# 9_Axis_Sensor.net
KiCad netlist of a schematic drawn in Altium Designer
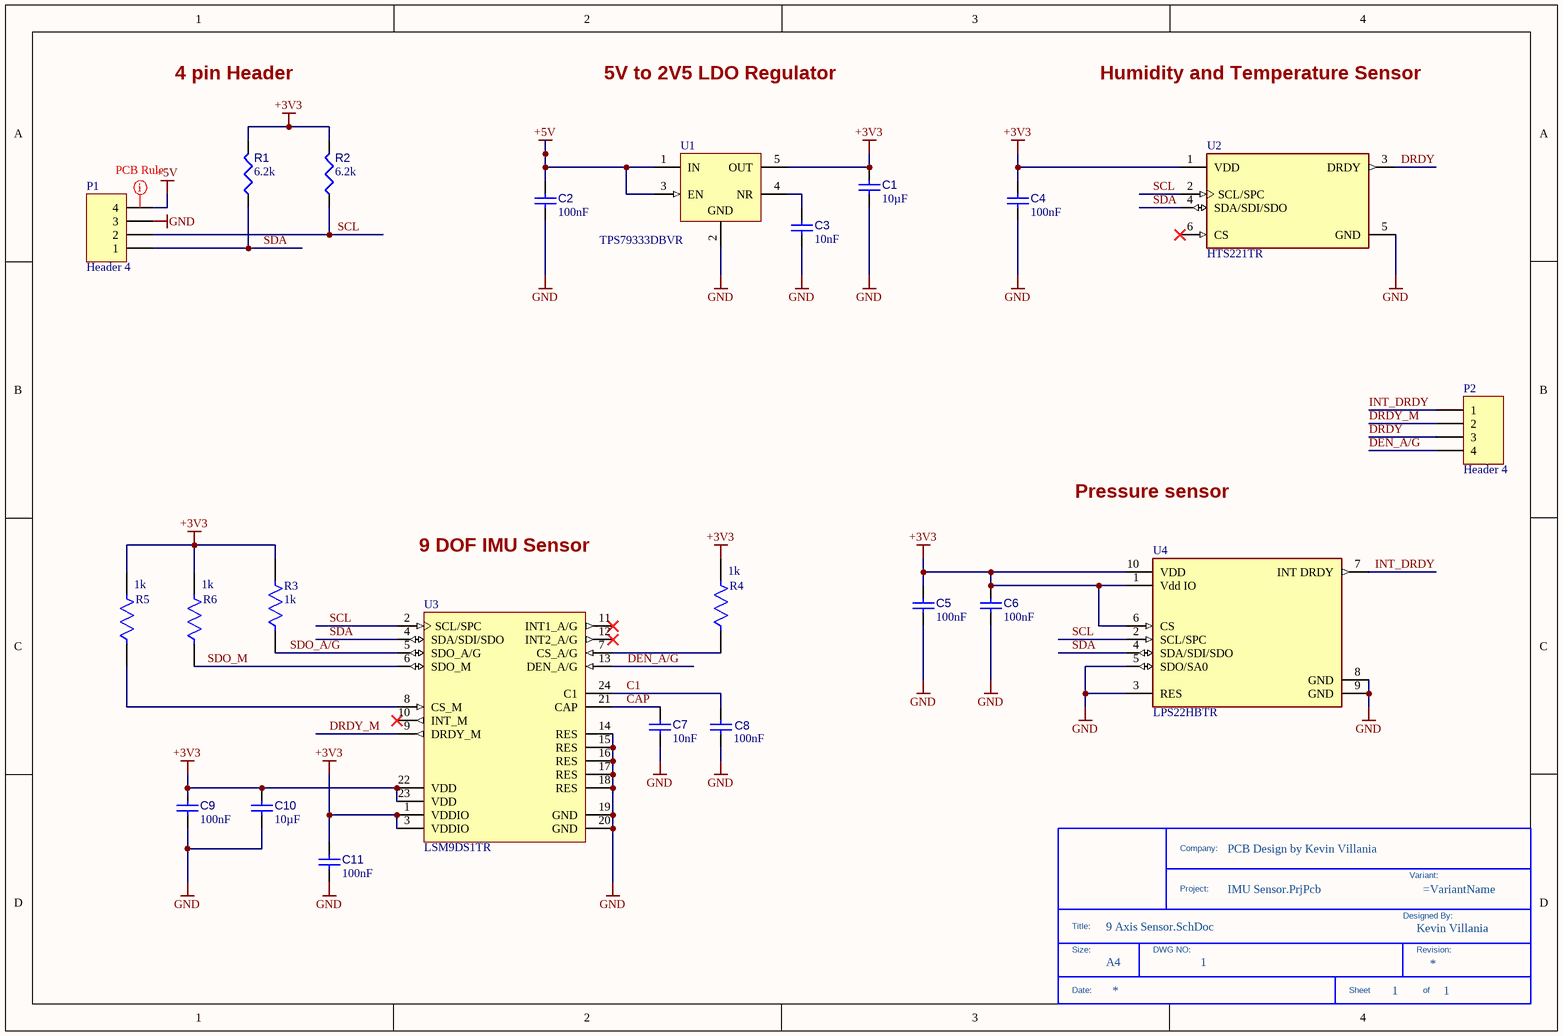
[diagram p0: 9 Axis Sensor.SchDoc]

(export (version "E")
  (design (tool "Eeschema 10.0.6"))
  (components
    (comp (ref "*")
      (value "Title Block")
      (description "Standard Title Block")
      (fields
        (field (name "DESIGNED BY") "Kevin Villania")
        (field (name "DWG NO") "1")
        (field (name "SIZE") "A4")
      )
      (libsource (lib "Standard Title Block Template") (part "Title Block"))
    )
    (comp (ref "C1")
      (value "10µF")
      (footprint "CAPC0402(1005)60_L")
      (description "Chip Capacitor, 10µF +/-40%, 6.3V, 0402, Thickness 0.6 mm")
      (fields (field (name "TOLERANCE") "10%") (field (name "Comment") "Capacitor 10µF +/-40% 6.3V 0402"))
      (libsource (lib "Polytechnic University of the Philippines") (part "CAP-NP-2"))
    )
    (comp (ref "C2")
      (value "100nF")
      (footprint "CAPC0402(1005)60_L")
      (description "Chip Capacitor, 100nF +/-20%, 10V, 0402, Thickness 0.6 mm")
      (fields (field (name "TOLERANCE") "20%") (field (name "Comment") "Capacitor 100nF +/-20% 10V 0402"))
      (libsource (lib "Polytechnic University of the Philippines") (part "CAP-NP-2"))
    )
    (comp (ref "C3")
      (value "10nF")
      (footprint "CAPC0402(1005)60_L")
      (description "Chip Capacitor, 10nF +/-20%, 50V, 0402, Thickness 0.6 mm")
      (fields (field (name "TOLERANCE") "5%") (field (name "Comment") "Capacitor 10nF +/-20% 50V 0402"))
      (libsource (lib "Polytechnic University of the Philippines") (part "CAP-NP-2"))
    )
    (comp (ref "C4")
      (value "100nF")
      (footprint "CAPC0402(1005)60_L")
      (description "Chip Capacitor, 100nF +/-20%, 10V, 0402, Thickness 0.6 mm")
      (fields (field (name "TOLERANCE") "20%") (field (name "Comment") "Capacitor 100nF +/-20% 10V 0402"))
      (libsource (lib "Polytechnic University of the Philippines") (part "CAP-NP-2"))
    )
    (comp (ref "C5")
      (value "100nF")
      (footprint "CAPC0402(1005)60_L")
      (description "Chip Capacitor, 100nF +/-20%, 10V, 0402, Thickness 0.6 mm")
      (fields (field (name "TOLERANCE") "20%") (field (name "Comment") "Capacitor 100nF +/-20% 10V 0402"))
      (libsource (lib "Polytechnic University of the Philippines") (part "CAP-NP-2"))
    )
    (comp (ref "C6")
      (value "100nF")
      (footprint "CAPC0402(1005)60_L")
      (description "Chip Capacitor, 100nF +/-20%, 10V, 0402, Thickness 0.6 mm")
      (fields (field (name "TOLERANCE") "20%") (field (name "Comment") "Capacitor 100nF +/-20% 10V 0402"))
      (libsource (lib "Polytechnic University of the Philippines") (part "CAP-NP-2"))
    )
    (comp (ref "C7")
      (value "10nF")
      (footprint "CAPC0402(1005)60_L")
      (description "Chip Capacitor, 10nF +/-20%, 50V, 0402, Thickness 0.6 mm")
      (fields (field (name "TOLERANCE") "5%") (field (name "Comment") "Capacitor 10nF +/-20% 50V 0402"))
      (libsource (lib "Polytechnic University of the Philippines") (part "CAP-NP-2"))
    )
    (comp (ref "C8")
      (value "100nF")
      (footprint "CAPC0402(1005)60_L")
      (description "Chip Capacitor, 100nF +/-20%, 10V, 0402, Thickness 0.6 mm")
      (fields (field (name "TOLERANCE") "20%") (field (name "Comment") "Capacitor 100nF +/-20% 10V 0402"))
      (libsource (lib "Polytechnic University of the Philippines") (part "CAP-NP-2"))
    )
    (comp (ref "C9")
      (value "100nF")
      (footprint "CAPC0402(1005)60_L")
      (description "Chip Capacitor, 100nF +/-20%, 10V, 0402, Thickness 0.6 mm")
      (fields (field (name "TOLERANCE") "20%") (field (name "Comment") "Capacitor 100nF +/-20% 10V 0402"))
      (libsource (lib "Polytechnic University of the Philippines") (part "CAP-NP-2"))
    )
    (comp (ref "C10")
      (value "10µF")
      (footprint "CAPC0603(1608)100_L")
      (description "Chip Capacitor, 10µF +/-20%, 10V, 0603, Thickness 1 mm")
      (fields (field (name "TOLERANCE") "10%") (field (name "Comment") "Capacitor 10µF +/-20% 10V 0603"))
      (libsource (lib "Polytechnic University of the Philippines") (part "CAP-NP-2"))
    )
    (comp (ref "C11")
      (value "100nF")
      (footprint "CAPC0402(1005)60_L")
      (description "Chip Capacitor, 100nF +/-20%, 10V, 0402, Thickness 0.6 mm")
      (fields (field (name "TOLERANCE") "20%") (field (name "Comment") "Capacitor 100nF +/-20% 10V 0402"))
      (libsource (lib "Polytechnic University of the Philippines") (part "CAP-NP-2"))
    )
    (comp (ref "P1")
      (value "Header 4")
      (footprint "HDR1X4")
      (description "Header, 4-Pin")
      (fields (field (name "PUBLISHER") "Altium Limited"))
      (libsource (lib "Miscellaneous Connectors") (part "Header 4"))
    )
    (comp (ref "P2")
      (value "Header 4")
      (footprint "HDR1X4")
      (description "Header, 4-Pin")
      (fields (field (name "PUBLISHER") "Altium Limited"))
      (libsource (lib "") (part "Header 4_1"))
    )
    (comp (ref "R1")
      (value "6.2k")
      (footprint "RESC0402(1005)_L")
      (description "Chip Resistor, 6,2 kOhms, +/-5 %, 63 mW, -55 to 155 degC, 0402")
      (fields (field (name "TOLERANCE") "5%") (field (name "POWER") "63mW"))
      (libsource (lib "Polytechnic University of the Philippines") (part "RES-2"))
    )
    (comp (ref "R2")
      (value "6.2k")
      (footprint "RESC0402(1005)_L")
      (description "Chip Resistor, 6,2 kOhms, +/-5 %, 63 mW, -55 to 155 degC, 0402")
      (fields (field (name "TOLERANCE") "5%") (field (name "POWER") "63mW"))
      (libsource (lib "Polytechnic University of the Philippines") (part "RES-2"))
    )
    (comp (ref "R3")
      (value "1k")
      (footprint "FP-RC1005-IPC_A")
      (description "Res Thick Film 0402 1kΩ 1% 0.063W ±100ppm/°C Molded SMD T/R")
      (fields (field (name "TOLERANCE") "1%"))
      (libsource (lib "Altium Content Vault") (part "1029c3af85768c4190bb7ad29bc67b5"))
    )
    (comp (ref "R4")
      (value "1k")
      (footprint "FP-RC1005-IPC_A")
      (description "Res Thick Film 0402 1kΩ 1% 0.063W ±100ppm/°C Molded SMD T/R")
      (fields (field (name "TOLERANCE") "1%"))
      (libsource (lib "Altium Content Vault") (part "1029c3af85768c4190bb7ad29bc67b5"))
    )
    (comp (ref "R5")
      (value "1k")
      (footprint "FP-RC1005-IPC_A")
      (description "Res Thick Film 0402 1kΩ 1% 0.063W ±100ppm/°C Molded SMD T/R")
      (fields (field (name "TOLERANCE") "1%"))
      (libsource (lib "Altium Content Vault") (part "1029c3af85768c4190bb7ad29bc67b5"))
    )
    (comp (ref "R6")
      (value "1k")
      (footprint "FP-RC1005-IPC_A")
      (description "Res Thick Film 0402 1kΩ 1% 0.063W ±100ppm/°C Molded SMD T/R")
      (fields (field (name "TOLERANCE") "1%"))
      (libsource (lib "Altium Content Vault") (part "1029c3af85768c4190bb7ad29bc67b5"))
    )
    (comp (ref "U1")
      (value "TPS79333DBVR")
      (footprint "DBV0005A_M")
      (fields (field (name "MANUFACTURER") "Texas Instruments"))
      (libsource (lib "Altium Content Vault") (part "TI-TPS79NXX-YYSOT5"))
    )
    (comp (ref "U2")
      (value "HTS221TR")
      (footprint "FP-HTS221TR-MFG")
      (description "SENS HUMI/TEMP 2.5V I2C 4.5% SMD")
      (libsource (lib "Altium Content Vault") (part "2053849febfc3e541f8558c6e004e7c"))
    )
    (comp (ref "U3")
      (value "LSM9DS1TR")
      (footprint "STM-LGA-24_3500X3000X1000")
      (fields (field (name "PARTNUMBER") "LSM9DS1") (field (name "MANUFACTURER") "STMicroelectronics"))
      (libsource (lib "Altium Content Vault") (part "STM-LSM9DS1-24"))
    )
    (comp (ref "U4")
      (value "LPS22HBTR")
      (footprint "FP-HLGA-10L-8479831-0")
      (description "MEMS NANO PRESSURE SENSOR: 260-1")
      (fields
        (field (name "OCTOPART") "https://octopart.com/lps22hbtr-stmicroelectronics-51851131")
        (field (name "MANUFACTURER") "STMicroelectronics")
      )
      (libsource (lib "Altium Content Vault") (part "d4c28707ea3ba579869663dd93796c5"))
    )
  )
  (nets
    (net (code "1") (name "+3V3") (class "Default")
      (node (ref "C1") (pin "2") (pinfunction "2_2") (pintype "passive"))
      (node (ref "C10") (pin "2") (pinfunction "2_2") (pintype "passive"))
      (node (ref "C11") (pin "1") (pinfunction "1_1") (pintype "passive"))
      (node (ref "C4") (pin "1") (pinfunction "1_1") (pintype "passive"))
      (node (ref "C5") (pin "1") (pinfunction "1_1") (pintype "passive"))
      (node (ref "C6") (pin "1") (pinfunction "1_1") (pintype "passive"))
      (node (ref "C9") (pin "1") (pinfunction "1_1") (pintype "passive"))
      (node (ref "R1") (pin "2") (pinfunction "2_2") (pintype "passive"))
      (node (ref "R2") (pin "2") (pinfunction "2_2") (pintype "passive"))
      (node (ref "R3") (pin "2") (pinfunction "2_2") (pintype "passive"))
      (node (ref "R4") (pin "2") (pinfunction "2_2") (pintype "passive"))
      (node (ref "R5") (pin "2") (pinfunction "2_2") (pintype "passive"))
      (node (ref "R6") (pin "2") (pinfunction "2_2") (pintype "passive"))
      (node (ref "U1") (pin "5") (pinfunction "OUT_5") (pintype "power_in"))
      (node (ref "U2") (pin "1") (pinfunction "VDD_1") (pintype "power_in"))
      (node (ref "U3") (pin "1") (pinfunction "VDDIO_1") (pintype "power_in"))
      (node (ref "U3") (pin "22") (pinfunction "VDD_22") (pintype "power_in"))
      (node (ref "U3") (pin "23") (pinfunction "VDD_23") (pintype "power_in"))
      (node (ref "U3") (pin "3") (pinfunction "VDDIO_3") (pintype "power_in"))
      (node (ref "U4") (pin "1") (pinfunction "Vdd_IO_1") (pintype "power_in"))
      (node (ref "U4") (pin "10") (pinfunction "VDD_10") (pintype "power_in"))
      (node (ref "U4") (pin "6") (pinfunction "CS_6") (pintype "input"))
    )
    (net (code "2") (name "+5V") (class "Default")
      (node (ref "C2") (pin "1") (pinfunction "1_1") (pintype "passive"))
      (node (ref "P1") (pin "4") (pinfunction "4_4") (pintype "passive"))
      (node (ref "U1") (pin "1") (pinfunction "IN_1") (pintype "power_in"))
      (node (ref "U1") (pin "3") (pinfunction "EN_3") (pintype "input"))
    )
    (net (code "3") (name "/C1") (class "Default")
      (node (ref "C8") (pin "1") (pinfunction "1_1") (pintype "passive"))
      (node (ref "U3") (pin "24") (pinfunction "C1_24") (pintype "passive"))
    )
    (net (code "4") (name "/CAP") (class "Default")
      (node (ref "C7") (pin "2") (pinfunction "2_2") (pintype "passive"))
      (node (ref "U3") (pin "21") (pinfunction "CAP_21") (pintype "passive"))
    )
    (net (code "5") (name "/DEN_A{slash}G") (class "Default")
      (node (ref "P2") (pin "4") (pinfunction "4_4") (pintype "passive"))
      (node (ref "U3") (pin "13") (pinfunction "DEN_A/G_13") (pintype "input"))
    )
    (net (code "6") (name "/DRDY") (class "Default")
      (node (ref "P2") (pin "3") (pinfunction "3_3") (pintype "passive"))
      (node (ref "U2") (pin "3") (pinfunction "DRDY_3") (pintype "output"))
    )
    (net (code "7") (name "/DRDY_M") (class "Default")
      (node (ref "P2") (pin "2") (pinfunction "2_2") (pintype "passive"))
      (node (ref "U3") (pin "9") (pinfunction "DRDY_M_9") (pintype "output"))
    )
    (net (code "8") (name "/INT_DRDY") (class "Default")
      (node (ref "P2") (pin "1") (pinfunction "1_1") (pintype "passive"))
      (node (ref "U4") (pin "7") (pinfunction "INT_DRDY_7") (pintype "output"))
    )
    (net (code "9") (name "/SCL") (class "Default")
      (node (ref "P1") (pin "2") (pinfunction "2_2") (pintype "passive"))
      (node (ref "R2") (pin "1") (pinfunction "1_1") (pintype "passive"))
      (node (ref "U2") (pin "2") (pinfunction "SCL/SPC_2") (pintype "input"))
      (node (ref "U3") (pin "2") (pinfunction "SCL/SPC_2") (pintype "input"))
      (node (ref "U4") (pin "2") (pinfunction "SCL/SPC_2") (pintype "input"))
    )
    (net (code "10") (name "/SDA") (class "Default")
      (node (ref "P1") (pin "1") (pinfunction "1_1") (pintype "passive"))
      (node (ref "R1") (pin "1") (pinfunction "1_1") (pintype "passive"))
      (node (ref "U2") (pin "4") (pinfunction "SDA/SDI/SDO_4") (pintype "bidirectional"))
      (node (ref "U3") (pin "4") (pinfunction "SDA/SDI/SDO_4") (pintype "bidirectional"))
      (node (ref "U4") (pin "4") (pinfunction "SDA/SDI/SDO_4") (pintype "bidirectional"))
    )
    (net (code "11") (name "/SDO_A{slash}G") (class "Default")
      (node (ref "R3") (pin "1") (pinfunction "1_1") (pintype "passive"))
      (node (ref "U3") (pin "5") (pinfunction "SDO_A/G_5") (pintype "bidirectional"))
    )
    (net (code "12") (name "/SDO_M") (class "Default")
      (node (ref "R6") (pin "1") (pinfunction "1_1") (pintype "passive"))
      (node (ref "U3") (pin "6") (pinfunction "SDO_M_6") (pintype "bidirectional"))
    )
    (net (code "13") (name "GND") (class "Default")
      (node (ref "C1") (pin "1") (pinfunction "1_1") (pintype "passive"))
      (node (ref "C10") (pin "1") (pinfunction "1_1") (pintype "passive"))
      (node (ref "C11") (pin "2") (pinfunction "2_2") (pintype "passive"))
      (node (ref "C2") (pin "2") (pinfunction "2_2") (pintype "passive"))
      (node (ref "C3") (pin "1") (pinfunction "1_1") (pintype "passive"))
      (node (ref "C4") (pin "2") (pinfunction "2_2") (pintype "passive"))
      (node (ref "C5") (pin "2") (pinfunction "2_2") (pintype "passive"))
      (node (ref "C6") (pin "2") (pinfunction "2_2") (pintype "passive"))
      (node (ref "C7") (pin "1") (pinfunction "1_1") (pintype "passive"))
      (node (ref "C8") (pin "2") (pinfunction "2_2") (pintype "passive"))
      (node (ref "C9") (pin "2") (pinfunction "2_2") (pintype "passive"))
      (node (ref "P1") (pin "3") (pinfunction "3_3") (pintype "passive"))
      (node (ref "U1") (pin "2") (pinfunction "GND_2") (pintype "power_in"))
      (node (ref "U2") (pin "5") (pinfunction "GND_5") (pintype "power_in"))
      (node (ref "U3") (pin "14") (pinfunction "RES_14") (pintype "passive"))
      (node (ref "U3") (pin "15") (pinfunction "RES_15") (pintype "passive"))
      (node (ref "U3") (pin "16") (pinfunction "RES_16") (pintype "passive"))
      (node (ref "U3") (pin "17") (pinfunction "RES_17") (pintype "passive"))
      (node (ref "U3") (pin "18") (pinfunction "RES_18") (pintype "passive"))
      (node (ref "U3") (pin "19") (pinfunction "GND_19") (pintype "power_in"))
      (node (ref "U3") (pin "20") (pinfunction "GND_20") (pintype "power_in"))
      (node (ref "U4") (pin "3") (pinfunction "RES_3") (pintype "passive"))
      (node (ref "U4") (pin "5") (pinfunction "SDO/SA0_5") (pintype "bidirectional"))
      (node (ref "U4") (pin "8") (pinfunction "GND_8") (pintype "power_in"))
      (node (ref "U4") (pin "9") (pinfunction "GND_9") (pintype "power_in"))
    )
    (net (code "14") (name "Net-(U1-NR)") (class "Default")
      (node (ref "C3") (pin "2") (pinfunction "2_2") (pintype "passive"))
      (node (ref "U1") (pin "4") (pinfunction "NR_4") (pintype "passive"))
    )
    (net (code "15") (name "Net-(U3-CS_A{slash}G)") (class "Default")
      (node (ref "R4") (pin "1") (pinfunction "1_1") (pintype "passive"))
      (node (ref "U3") (pin "7") (pinfunction "CS_A/G_7") (pintype "input"))
    )
    (net (code "16") (name "Net-(U3-CS_M)") (class "Default")
      (node (ref "R5") (pin "1") (pinfunction "1_1") (pintype "passive"))
      (node (ref "U3") (pin "8") (pinfunction "CS_M_8") (pintype "input"))
    )
    (net (code "17") (name "unconnected-(U2-CS-Pad6)") (class "Default")
      (node (ref "U2") (pin "6") (pinfunction "CS_6") (pintype "input+no_connect"))
    )
    (net (code "18") (name "unconnected-(U3-INT1_A{slash}G-Pad11)") (class "Default")
      (node (ref "U3") (pin "11") (pinfunction "INT1_A/G_11") (pintype "output+no_connect"))
    )
    (net (code "19") (name "unconnected-(U3-INT2_A{slash}G-Pad12)") (class "Default")
      (node (ref "U3") (pin "12") (pinfunction "INT2_A/G_12") (pintype "output+no_connect"))
    )
    (net (code "20") (name "unconnected-(U3-INT_M-Pad10)") (class "Default")
      (node (ref "U3") (pin "10") (pinfunction "INT_M_10") (pintype "output+no_connect"))
    )
  )
)
